# capsense-board.net
KiCad netlist of a schematic drawn in EAGLE
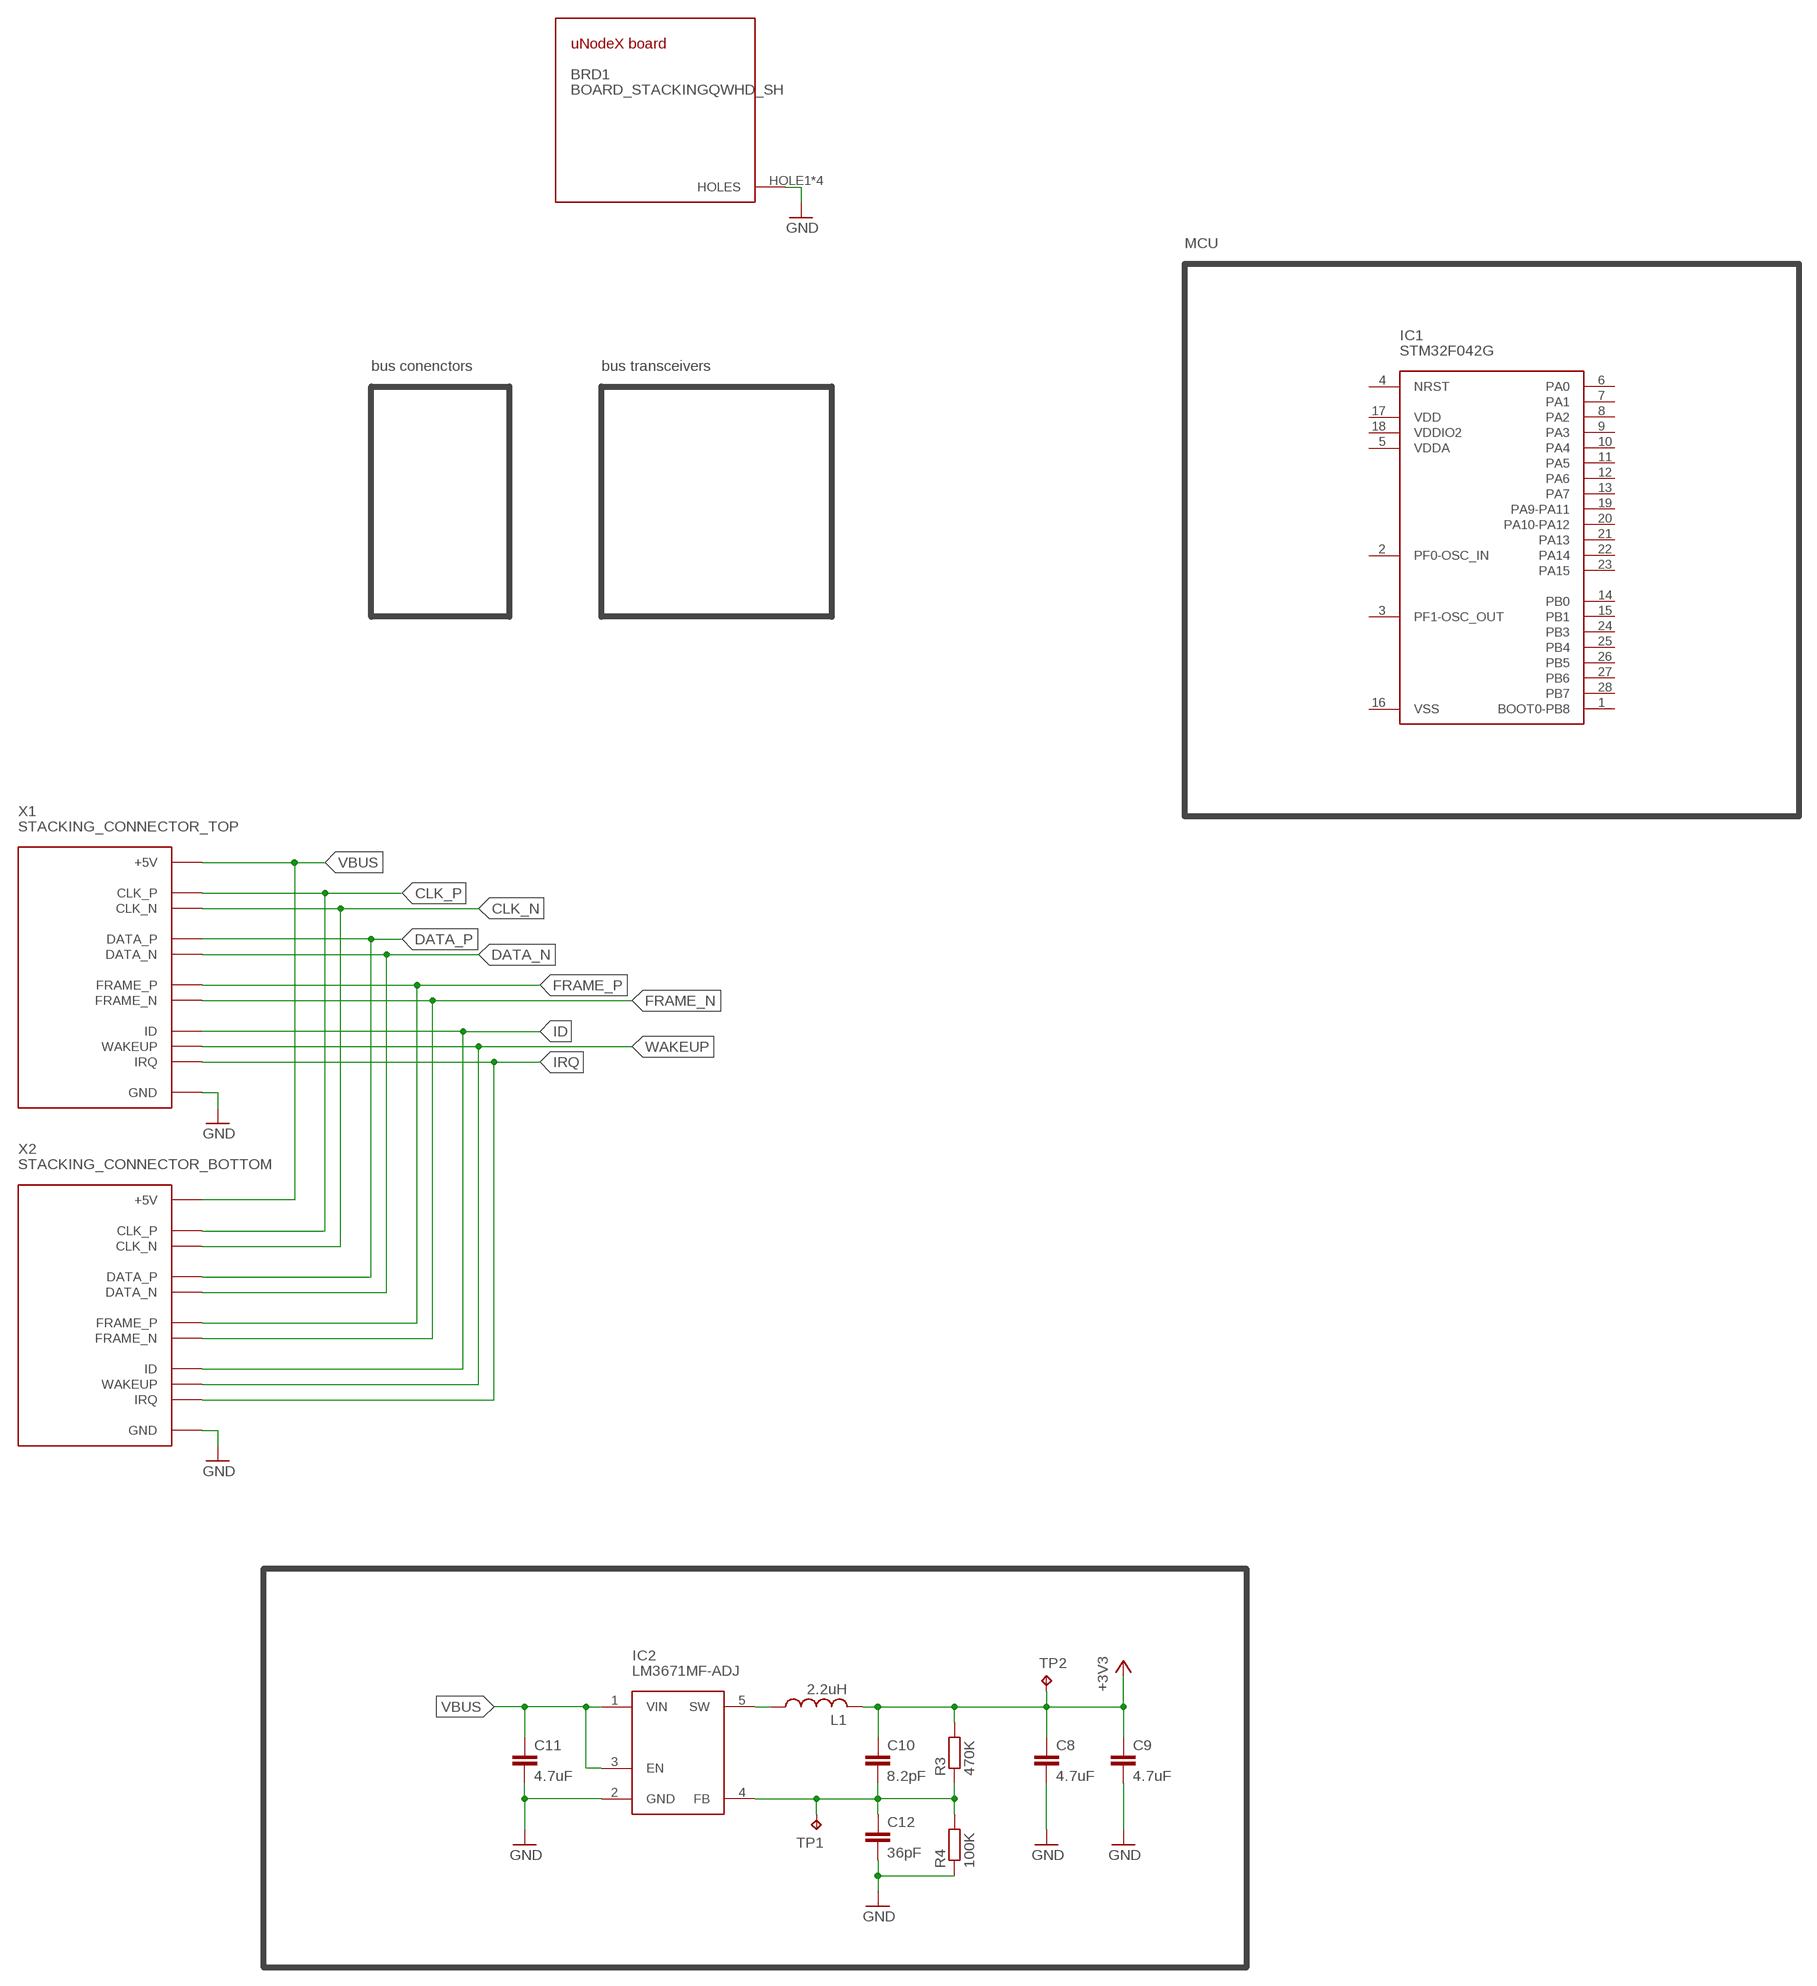
[diagram p0: schematic, sheet 1]

(export (version "E")
  (design (tool "Eeschema 10.0.6"))
  (components
    (comp (ref "BRD1")
      (value "BOARD_STACKINGQWHD_SH")
      (footprint "eagle-import:QWHD_SHARP_CORNERS")
      (libsource (lib "eagle-import") (part "BOARD_STACKINGQWHD_SH"))
    )
    (comp (ref "C8")
      (value "4.7uF")
      (footprint "eagle-import:C0805")
      (libsource (lib "eagle-import") (part "C-EUC0805"))
    )
    (comp (ref "C9")
      (value "4.7uF")
      (footprint "eagle-import:C0805")
      (libsource (lib "eagle-import") (part "C-EUC0805"))
    )
    (comp (ref "C10")
      (value "8.2pF")
      (footprint "eagle-import:C0603")
      (libsource (lib "eagle-import") (part "C-EUC0603"))
    )
    (comp (ref "C11")
      (value "4.7uF")
      (footprint "eagle-import:C0805")
      (libsource (lib "eagle-import") (part "C-EUC0805"))
    )
    (comp (ref "C12")
      (value "36pF")
      (footprint "eagle-import:C0603")
      (libsource (lib "eagle-import") (part "C-EUC0603"))
    )
    (comp (ref "IC1")
      (value "STM32F042G")
      (footprint "eagle-import:UFQFPN28")
      (libsource (lib "eagle-import") (part "STM32F042G"))
    )
    (comp (ref "IC2")
      (value "LM3671MF-ADJ")
      (footprint "eagle-import:SOT23-5")
      (libsource (lib "eagle-import") (part "LM3671MF"))
    )
    (comp (ref "L1")
      (value "2.2uH")
      (footprint "eagle-import:L2012C")
      (libsource (lib "eagle-import") (part "L-USL2012C"))
    )
    (comp (ref "R3")
      (value "470K")
      (footprint "eagle-import:R0603")
      (libsource (lib "eagle-import") (part "R-EU_R0603"))
    )
    (comp (ref "R4")
      (value "100K")
      (footprint "eagle-import:R0603")
      (libsource (lib "eagle-import") (part "R-EU_R0603"))
    )
    (comp (ref "TP1")
      (value "TPB1,27")
      (footprint "eagle-import:B1,27")
      (libsource (lib "eagle-import") (part "TPB1,27"))
    )
    (comp (ref "TP2")
      (value "TPB1,27")
      (footprint "eagle-import:B1,27")
      (libsource (lib "eagle-import") (part "TPB1,27"))
    )
    (comp (ref "X1")
      (value "STACKING_CONNECTOR_TOP")
      (footprint "eagle-import:HAR-FLEX-TOP-12P")
      (libsource (lib "eagle-import") (part "STACKING_CONNECTOR_TOP"))
    )
    (comp (ref "X2")
      (value "STACKING_CONNECTOR_BOTTOM")
      (footprint "eagle-import:HAR-FLEX-BOTTOM-12P")
      (libsource (lib "eagle-import") (part "STACKING_CONNECTOR_BOTTOM"))
    )
  )
  (nets
    (net (code "1") (name "+3V3") (class "Default")
      (node (ref "C10") (pin "1") (pinfunction "1_1") (pintype "passive"))
      (node (ref "C8") (pin "1") (pinfunction "1_1") (pintype "passive"))
      (node (ref "C9") (pin "1") (pinfunction "1_1") (pintype "passive"))
      (node (ref "L1") (pin "2") (pinfunction "2_2") (pintype "passive"))
      (node (ref "R3") (pin "2") (pinfunction "2_2") (pintype "passive"))
      (node (ref "TP2") (pin "TP") (pinfunction "TP_TP") (pintype "input"))
    )
    (net (code "2") (name "CLK_N") (class "Default")
      (node (ref "X1") (pin "CLK_N") (pinfunction "CLK_N_CLK_N") (pintype "bidirectional"))
      (node (ref "X2") (pin "CLK_N") (pinfunction "CLK_N_CLK_N") (pintype "bidirectional"))
    )
    (net (code "3") (name "CLK_P") (class "Default")
      (node (ref "X1") (pin "CLK_P") (pinfunction "CLK_P_CLK_P") (pintype "bidirectional"))
      (node (ref "X2") (pin "CLK_P") (pinfunction "CLK_P_CLK_P") (pintype "bidirectional"))
    )
    (net (code "4") (name "DATA_N") (class "Default")
      (node (ref "X1") (pin "DATA_N") (pinfunction "DATA_N_DATA_N") (pintype "bidirectional"))
      (node (ref "X2") (pin "DATA_N") (pinfunction "DATA_N_DATA_N") (pintype "bidirectional"))
    )
    (net (code "5") (name "DATA_P") (class "Default")
      (node (ref "X1") (pin "DATA_P") (pinfunction "DATA_P_DATA_P") (pintype "bidirectional"))
      (node (ref "X2") (pin "DATA_P") (pinfunction "DATA_P_DATA_P") (pintype "bidirectional"))
    )
    (net (code "6") (name "FRAME_N") (class "Default")
      (node (ref "X1") (pin "FRAME_N") (pinfunction "FRAME_N_FRAME_N") (pintype "bidirectional"))
      (node (ref "X2") (pin "FRAME_N") (pinfunction "FRAME_N_FRAME_N") (pintype "bidirectional"))
    )
    (net (code "7") (name "FRAME_P") (class "Default")
      (node (ref "X1") (pin "FRAME_P") (pinfunction "FRAME_P_FRAME_P") (pintype "bidirectional"))
      (node (ref "X2") (pin "FRAME_P") (pinfunction "FRAME_P_FRAME_P") (pintype "bidirectional"))
    )
    (net (code "8") (name "GND") (class "Default")
      (node (ref "BRD1") (pin "HOLE1") (pinfunction "HOLES_HOLE1") (pintype "bidirectional"))
      (node (ref "BRD1") (pin "HOLE2") (pinfunction "HOLES_HOLE2") (pintype "bidirectional"))
      (node (ref "BRD1") (pin "HOLE3") (pinfunction "HOLES_HOLE3") (pintype "bidirectional"))
      (node (ref "BRD1") (pin "HOLE4") (pinfunction "HOLES_HOLE4") (pintype "bidirectional"))
      (node (ref "C11") (pin "2") (pinfunction "2_2") (pintype "passive"))
      (node (ref "C12") (pin "2") (pinfunction "2_2") (pintype "passive"))
      (node (ref "C8") (pin "2") (pinfunction "2_2") (pintype "passive"))
      (node (ref "C9") (pin "2") (pinfunction "2_2") (pintype "passive"))
      (node (ref "IC2") (pin "2") (pinfunction "GND_2") (pintype "bidirectional"))
      (node (ref "R4") (pin "1") (pinfunction "1_1") (pintype "passive"))
      (node (ref "X1") (pin "GND1") (pinfunction "GND_GND1") (pintype "bidirectional"))
      (node (ref "X1") (pin "GND2") (pinfunction "GND_GND2") (pintype "bidirectional"))
      (node (ref "X1") (pin "H1") (pinfunction "GND_H1") (pintype "bidirectional"))
      (node (ref "X1") (pin "H2") (pinfunction "GND_H2") (pintype "bidirectional"))
      (node (ref "X1") (pin "H3") (pinfunction "GND_H3") (pintype "bidirectional"))
      (node (ref "X1") (pin "H4") (pinfunction "GND_H4") (pintype "bidirectional"))
      (node (ref "X2") (pin "GND1") (pinfunction "GND_GND1") (pintype "bidirectional"))
      (node (ref "X2") (pin "GND2") (pinfunction "GND_GND2") (pintype "bidirectional"))
      (node (ref "X2") (pin "H1") (pinfunction "GND_H1") (pintype "bidirectional"))
      (node (ref "X2") (pin "H2") (pinfunction "GND_H2") (pintype "bidirectional"))
      (node (ref "X2") (pin "H3") (pinfunction "GND_H3") (pintype "bidirectional"))
      (node (ref "X2") (pin "H4") (pinfunction "GND_H4") (pintype "bidirectional"))
    )
    (net (code "9") (name "ID") (class "Default")
      (node (ref "X1") (pin "ID") (pinfunction "ID_ID") (pintype "bidirectional"))
      (node (ref "X2") (pin "ID") (pinfunction "ID_ID") (pintype "bidirectional"))
    )
    (net (code "10") (name "IRQ") (class "Default")
      (node (ref "X1") (pin "IRQ") (pinfunction "IRQ_IRQ") (pintype "bidirectional"))
      (node (ref "X2") (pin "IRQ") (pinfunction "IRQ_IRQ") (pintype "bidirectional"))
    )
    (net (code "11") (name "Net-(IC2-FB)") (class "Default")
      (node (ref "C10") (pin "2") (pinfunction "2_2") (pintype "passive"))
      (node (ref "C12") (pin "1") (pinfunction "1_1") (pintype "passive"))
      (node (ref "IC2") (pin "4") (pinfunction "FB_4") (pintype "bidirectional"))
      (node (ref "R3") (pin "1") (pinfunction "1_1") (pintype "passive"))
      (node (ref "R4") (pin "2") (pinfunction "2_2") (pintype "passive"))
      (node (ref "TP1") (pin "TP") (pinfunction "TP_TP") (pintype "input"))
    )
    (net (code "12") (name "Net-(IC2-SW)") (class "Default")
      (node (ref "IC2") (pin "5") (pinfunction "SW_5") (pintype "bidirectional"))
      (node (ref "L1") (pin "1") (pinfunction "1_1") (pintype "passive"))
    )
    (net (code "13") (name "VBUS") (class "Default")
      (node (ref "C11") (pin "1") (pinfunction "1_1") (pintype "passive"))
      (node (ref "IC2") (pin "1") (pinfunction "VIN_1") (pintype "bidirectional"))
      (node (ref "IC2") (pin "3") (pinfunction "EN_3") (pintype "bidirectional"))
      (node (ref "X1") (pin "+5V") (pinfunction "+5V_+5V") (pintype "bidirectional"))
      (node (ref "X2") (pin "+5V") (pinfunction "+5V_+5V") (pintype "bidirectional"))
    )
    (net (code "14") (name "WAKEUP") (class "Default")
      (node (ref "X1") (pin "WAKEUP") (pinfunction "WAKEUP_WAKEUP") (pintype "bidirectional"))
      (node (ref "X2") (pin "WAKEUP") (pinfunction "WAKEUP_WAKEUP") (pintype "bidirectional"))
    )
    (net (code "15") (name "unconnected-(IC1-BOOT0-PB8-Pad1)") (class "Default")
      (node (ref "IC1") (pin "1") (pinfunction "BOOT0-PB8_1") (pintype "bidirectional"))
    )
    (net (code "16") (name "unconnected-(IC1-NRST-Pad4)") (class "Default")
      (node (ref "IC1") (pin "4") (pinfunction "NRST_4") (pintype "bidirectional"))
    )
    (net (code "17") (name "unconnected-(IC1-PA0-Pad6)") (class "Default")
      (node (ref "IC1") (pin "6") (pinfunction "PA0_6") (pintype "bidirectional"))
    )
    (net (code "18") (name "unconnected-(IC1-PA1-Pad7)") (class "Default")
      (node (ref "IC1") (pin "7") (pinfunction "PA1_7") (pintype "bidirectional"))
    )
    (net (code "19") (name "unconnected-(IC1-PA2-Pad8)") (class "Default")
      (node (ref "IC1") (pin "8") (pinfunction "PA2_8") (pintype "bidirectional"))
    )
    (net (code "20") (name "unconnected-(IC1-PA3-Pad9)") (class "Default")
      (node (ref "IC1") (pin "9") (pinfunction "PA3_9") (pintype "bidirectional"))
    )
    (net (code "21") (name "unconnected-(IC1-PA4-Pad10)") (class "Default")
      (node (ref "IC1") (pin "10") (pinfunction "PA4_10") (pintype "bidirectional"))
    )
    (net (code "22") (name "unconnected-(IC1-PA5-Pad11)") (class "Default")
      (node (ref "IC1") (pin "11") (pinfunction "PA5_11") (pintype "bidirectional"))
    )
    (net (code "23") (name "unconnected-(IC1-PA6-Pad12)") (class "Default")
      (node (ref "IC1") (pin "12") (pinfunction "PA6_12") (pintype "bidirectional"))
    )
    (net (code "24") (name "unconnected-(IC1-PA7-Pad13)") (class "Default")
      (node (ref "IC1") (pin "13") (pinfunction "PA7_13") (pintype "bidirectional"))
    )
    (net (code "25") (name "unconnected-(IC1-PA9-PA11-Pad19)") (class "Default")
      (node (ref "IC1") (pin "19") (pinfunction "PA9-PA11_19") (pintype "bidirectional"))
    )
    (net (code "26") (name "unconnected-(IC1-PA10-PA12-Pad20)") (class "Default")
      (node (ref "IC1") (pin "20") (pinfunction "PA10-PA12_20") (pintype "bidirectional"))
    )
    (net (code "27") (name "unconnected-(IC1-PA13-Pad21)") (class "Default")
      (node (ref "IC1") (pin "21") (pinfunction "PA13_21") (pintype "bidirectional"))
    )
    (net (code "28") (name "unconnected-(IC1-PA14-Pad22)") (class "Default")
      (node (ref "IC1") (pin "22") (pinfunction "PA14_22") (pintype "bidirectional"))
    )
    (net (code "29") (name "unconnected-(IC1-PA15-Pad23)") (class "Default")
      (node (ref "IC1") (pin "23") (pinfunction "PA15_23") (pintype "bidirectional"))
    )
    (net (code "30") (name "unconnected-(IC1-PB0-Pad14)") (class "Default")
      (node (ref "IC1") (pin "14") (pinfunction "PB0_14") (pintype "bidirectional"))
    )
    (net (code "31") (name "unconnected-(IC1-PB1-Pad15)") (class "Default")
      (node (ref "IC1") (pin "15") (pinfunction "PB1_15") (pintype "bidirectional"))
    )
    (net (code "32") (name "unconnected-(IC1-PB3-Pad24)") (class "Default")
      (node (ref "IC1") (pin "24") (pinfunction "PB3_24") (pintype "bidirectional"))
    )
    (net (code "33") (name "unconnected-(IC1-PB4-Pad25)") (class "Default")
      (node (ref "IC1") (pin "25") (pinfunction "PB4_25") (pintype "bidirectional"))
    )
    (net (code "34") (name "unconnected-(IC1-PB5-Pad26)") (class "Default")
      (node (ref "IC1") (pin "26") (pinfunction "PB5_26") (pintype "bidirectional"))
    )
    (net (code "35") (name "unconnected-(IC1-PB6-Pad27)") (class "Default")
      (node (ref "IC1") (pin "27") (pinfunction "PB6_27") (pintype "bidirectional"))
    )
    (net (code "36") (name "unconnected-(IC1-PB7-Pad28)") (class "Default")
      (node (ref "IC1") (pin "28") (pinfunction "PB7_28") (pintype "bidirectional"))
    )
    (net (code "37") (name "unconnected-(IC1-PF0-OSC_IN-Pad2)") (class "Default")
      (node (ref "IC1") (pin "2") (pinfunction "PF0-OSC_IN_2") (pintype "bidirectional"))
    )
    (net (code "38") (name "unconnected-(IC1-PF1-OSC_OUT-Pad3)") (class "Default")
      (node (ref "IC1") (pin "3") (pinfunction "PF1-OSC_OUT_3") (pintype "bidirectional"))
    )
    (net (code "39") (name "unconnected-(IC1-VDD-Pad17)") (class "Default")
      (node (ref "IC1") (pin "17") (pinfunction "VDD_17") (pintype "bidirectional"))
    )
    (net (code "40") (name "unconnected-(IC1-VDDA-Pad5)") (class "Default")
      (node (ref "IC1") (pin "5") (pinfunction "VDDA_5") (pintype "bidirectional"))
    )
    (net (code "41") (name "unconnected-(IC1-VDDIO2-Pad18)") (class "Default")
      (node (ref "IC1") (pin "18") (pinfunction "VDDIO2_18") (pintype "bidirectional"))
    )
    (net (code "42") (name "unconnected-(IC1-VSS-Pad16)") (class "Default")
      (node (ref "IC1") (pin "16") (pinfunction "VSS_16") (pintype "bidirectional"))
    )
  )
)
